# GD_Tcontroller_Sensor.net
KiCad netlist of a schematic drawn in Altium Designer
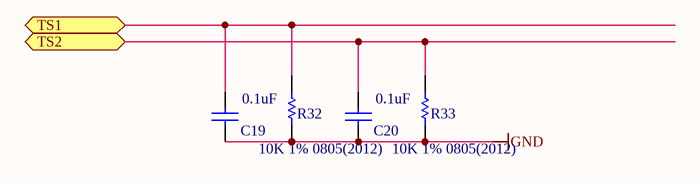
[diagram p0: GD_Tcontroller_Sensor.SchDoc]

(export (version "E")
  (design (tool "Eeschema 10.0.6"))
  (components
    (comp (ref "C19")
      (value "0.1uF")
      (footprint "C0805")
      (description "CAP 0.1uF 50V ±20% 0805 (2012 Metric) Thickness 1mm SMD")
      (fields (field (name "TOLERANCE") "20%") (field (name "Comment") "CAP 0.1uF 50V 0805(2012)"))
      (libsource (lib "Altium Content Vault") (part "CMP-1036-00070-1"))
    )
    (comp (ref "C20")
      (value "0.1uF")
      (footprint "C0805")
      (description "CAP 0.1uF 50V ±20% 0805 (2012 Metric) Thickness 1mm SMD")
      (fields (field (name "TOLERANCE") "20%") (field (name "Comment") "CAP 0.1uF 50V 0805(2012)"))
      (libsource (lib "Altium Content Vault") (part "CMP-1036-00070-1"))
    )
    (comp (ref "R32")
      (value "10K 1% 0805(2012)")
      (footprint "R0805")
      (description "10K 0.125W 5% 0805 (2012 Metric)  SMD")
      (fields (field (name "POWER") "0.125 W") (field (name "TOLERANCE") "1 %"))
      (libsource (lib "Altium Content Vault") (part "CMP-1013-00098-1"))
    )
    (comp (ref "R33")
      (value "10K 1% 0805(2012)")
      (footprint "R0805")
      (description "10K 0.125W 5% 0805 (2012 Metric)  SMD")
      (fields (field (name "POWER") "0.125 W") (field (name "TOLERANCE") "1 %"))
      (libsource (lib "Altium Content Vault") (part "CMP-1013-00098-1"))
    )
  )
  (nets
    (net (code "1") (name "/TS1") (class "Default")
      (node (ref "C19") (pin "2") (pinfunction "2_2") (pintype "passive"))
      (node (ref "R32") (pin "1") (pinfunction "1_1") (pintype "passive"))
    )
    (net (code "2") (name "/TS2") (class "Default")
      (node (ref "C20") (pin "2") (pinfunction "2_2") (pintype "passive"))
      (node (ref "R33") (pin "1") (pinfunction "1_1") (pintype "passive"))
    )
    (net (code "3") (name "GND") (class "Default")
      (node (ref "C19") (pin "1") (pinfunction "1_1") (pintype "passive"))
      (node (ref "C20") (pin "1") (pinfunction "1_1") (pintype "passive"))
      (node (ref "R32") (pin "2") (pinfunction "2_2") (pintype "passive"))
      (node (ref "R33") (pin "2") (pinfunction "2_2") (pintype "passive"))
    )
  )
)
